# Mother-board.net
KiCad netlist of a schematic drawn in EAGLE
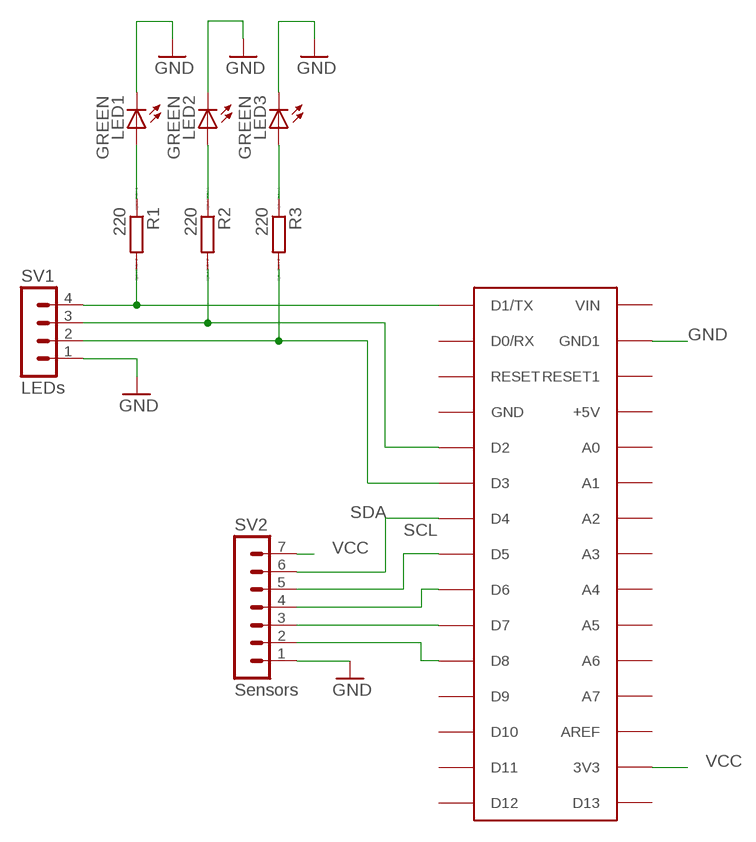
[diagram p0: schematic, sheet 1]

(export (version "E")
  (design (tool "Eeschema 10.0.6"))
  (components
    (comp (ref "LED1")
      (value "GREEN")
      (footprint "eagle-import:LED5MM")
      (libsource (lib "eagle-import") (part "LED5MM"))
    )
    (comp (ref "LED2")
      (value "GREEN")
      (footprint "eagle-import:LED5MM")
      (libsource (lib "eagle-import") (part "LED5MM"))
    )
    (comp (ref "LED3")
      (value "GREEN")
      (footprint "eagle-import:LED5MM")
      (libsource (lib "eagle-import") (part "LED5MM"))
    )
    (comp (ref "R1")
      (value "220")
      (footprint "eagle-import:R1005")
      (libsource (lib "eagle-import") (part "RR1005"))
    )
    (comp (ref "R2")
      (value "220")
      (footprint "eagle-import:R1005")
      (libsource (lib "eagle-import") (part "RR1005"))
    )
    (comp (ref "R3")
      (value "220")
      (footprint "eagle-import:R1005")
      (libsource (lib "eagle-import") (part "RR1005"))
    )
    (comp (ref "SV1")
      (value "LEDs")
      (footprint "eagle-import:MA04-1")
      (libsource (lib "eagle-import") (part "MA04-1"))
    )
    (comp (ref "SV2")
      (value "Sensors")
      (footprint "eagle-import:MA07-1")
      (libsource (lib "eagle-import") (part "MA07-1"))
    )
    (comp (ref "U$1")
      (value "ARDUINONANO")
      (footprint "eagle-import:PDIP-32")
      (libsource (lib "eagle-import") (part "ARDUINONANO"))
    )
  )
  (nets
    (net (code "1") (name "/SCL") (class "Default")
      (node (ref "SV2") (pin "5") (pinfunction "5_5") (pintype "passive"))
      (node (ref "U$1") (pin "D5") (pinfunction "D5_D5") (pintype "bidirectional"))
    )
    (net (code "2") (name "/SDA") (class "Default")
      (node (ref "SV2") (pin "6") (pinfunction "6_6") (pintype "passive"))
      (node (ref "U$1") (pin "D4") (pinfunction "D4_D4") (pintype "bidirectional"))
    )
    (net (code "3") (name "/VCC") (class "Default")
      (node (ref "SV2") (pin "7") (pinfunction "7_7") (pintype "passive"))
      (node (ref "U$1") (pin "3V3") (pinfunction "3V3_3V3") (pintype "bidirectional"))
    )
    (net (code "4") (name "GND") (class "Default")
      (node (ref "LED1") (pin "K") (pinfunction "C_K") (pintype "passive"))
      (node (ref "LED2") (pin "K") (pinfunction "C_K") (pintype "passive"))
      (node (ref "LED3") (pin "K") (pinfunction "C_K") (pintype "passive"))
      (node (ref "SV1") (pin "1") (pinfunction "1_1") (pintype "passive"))
      (node (ref "SV2") (pin "1") (pinfunction "1_1") (pintype "passive"))
      (node (ref "U$1") (pin "GND1") (pinfunction "GND1_GND1") (pintype "bidirectional"))
    )
    (net (code "5") (name "Net-(LED1-PadA)") (class "Default")
      (node (ref "LED1") (pin "A") (pinfunction "A_A") (pintype "passive"))
      (node (ref "R1") (pin "1") (pinfunction "1_1") (pintype "passive"))
    )
    (net (code "6") (name "Net-(LED2-PadA)") (class "Default")
      (node (ref "LED2") (pin "A") (pinfunction "A_A") (pintype "passive"))
      (node (ref "R2") (pin "1") (pinfunction "1_1") (pintype "passive"))
    )
    (net (code "7") (name "Net-(LED3-PadA)") (class "Default")
      (node (ref "LED3") (pin "A") (pinfunction "A_A") (pintype "passive"))
      (node (ref "R3") (pin "1") (pinfunction "1_1") (pintype "passive"))
    )
    (net (code "8") (name "Net-(R1-Pad2)") (class "Default")
      (node (ref "R1") (pin "2") (pinfunction "2_2") (pintype "passive"))
      (node (ref "SV1") (pin "4") (pinfunction "4_4") (pintype "passive"))
      (node (ref "U$1") (pin "D1/TX") (pinfunction "D1/TX_D1/TX") (pintype "bidirectional"))
    )
    (net (code "9") (name "Net-(R2-Pad2)") (class "Default")
      (node (ref "R2") (pin "2") (pinfunction "2_2") (pintype "passive"))
      (node (ref "SV1") (pin "3") (pinfunction "3_3") (pintype "passive"))
      (node (ref "U$1") (pin "D2") (pinfunction "D2_D2") (pintype "bidirectional"))
    )
    (net (code "10") (name "Net-(R3-Pad2)") (class "Default")
      (node (ref "R3") (pin "2") (pinfunction "2_2") (pintype "passive"))
      (node (ref "SV1") (pin "2") (pinfunction "2_2") (pintype "passive"))
      (node (ref "U$1") (pin "D3") (pinfunction "D3_D3") (pintype "bidirectional"))
    )
    (net (code "11") (name "Net-(SV2-Pad2)") (class "Default")
      (node (ref "SV2") (pin "2") (pinfunction "2_2") (pintype "passive"))
      (node (ref "U$1") (pin "D8") (pinfunction "D8_D8") (pintype "bidirectional"))
    )
    (net (code "12") (name "Net-(SV2-Pad3)") (class "Default")
      (node (ref "SV2") (pin "3") (pinfunction "3_3") (pintype "passive"))
      (node (ref "U$1") (pin "D7") (pinfunction "D7_D7") (pintype "bidirectional"))
    )
    (net (code "13") (name "Net-(SV2-Pad4)") (class "Default")
      (node (ref "SV2") (pin "4") (pinfunction "4_4") (pintype "passive"))
      (node (ref "U$1") (pin "D6") (pinfunction "D6_D6") (pintype "bidirectional"))
    )
    (net (code "14") (name "unconnected-(U$1-Pad+5V)") (class "Default")
      (node (ref "U$1") (pin "+5V") (pinfunction "+5V_+5V") (pintype "bidirectional"))
    )
    (net (code "15") (name "unconnected-(U$1-PadA0)") (class "Default")
      (node (ref "U$1") (pin "A0") (pinfunction "A0_A0") (pintype "bidirectional"))
    )
    (net (code "16") (name "unconnected-(U$1-PadA1)") (class "Default")
      (node (ref "U$1") (pin "A1") (pinfunction "A1_A1") (pintype "bidirectional"))
    )
    (net (code "17") (name "unconnected-(U$1-PadA2)") (class "Default")
      (node (ref "U$1") (pin "A2") (pinfunction "A2_A2") (pintype "bidirectional"))
    )
    (net (code "18") (name "unconnected-(U$1-PadA3)") (class "Default")
      (node (ref "U$1") (pin "A3") (pinfunction "A3_A3") (pintype "bidirectional"))
    )
    (net (code "19") (name "unconnected-(U$1-PadA4)") (class "Default")
      (node (ref "U$1") (pin "A4") (pinfunction "A4_A4") (pintype "bidirectional"))
    )
    (net (code "20") (name "unconnected-(U$1-PadA5)") (class "Default")
      (node (ref "U$1") (pin "A5") (pinfunction "A5_A5") (pintype "bidirectional"))
    )
    (net (code "21") (name "unconnected-(U$1-PadA6)") (class "Default")
      (node (ref "U$1") (pin "A6") (pinfunction "A6_A6") (pintype "bidirectional"))
    )
    (net (code "22") (name "unconnected-(U$1-PadA7)") (class "Default")
      (node (ref "U$1") (pin "A7") (pinfunction "A7_A7") (pintype "bidirectional"))
    )
    (net (code "23") (name "unconnected-(U$1-PadAREF)") (class "Default")
      (node (ref "U$1") (pin "AREF") (pinfunction "AREF_AREF") (pintype "bidirectional"))
    )
    (net (code "24") (name "unconnected-(U$1-PadD0{slash}RX)") (class "Default")
      (node (ref "U$1") (pin "D0/RX") (pinfunction "D0/RX_D0/RX") (pintype "bidirectional"))
    )
    (net (code "25") (name "unconnected-(U$1-PadD9)") (class "Default")
      (node (ref "U$1") (pin "D9") (pinfunction "D9_D9") (pintype "bidirectional"))
    )
    (net (code "26") (name "unconnected-(U$1-PadD10)") (class "Default")
      (node (ref "U$1") (pin "D10") (pinfunction "D10_D10") (pintype "bidirectional"))
    )
    (net (code "27") (name "unconnected-(U$1-PadD11)") (class "Default")
      (node (ref "U$1") (pin "D11") (pinfunction "D11_D11") (pintype "bidirectional"))
    )
    (net (code "28") (name "unconnected-(U$1-PadD12)") (class "Default")
      (node (ref "U$1") (pin "D12") (pinfunction "D12_D12") (pintype "bidirectional"))
    )
    (net (code "29") (name "unconnected-(U$1-PadD13)") (class "Default")
      (node (ref "U$1") (pin "D13") (pinfunction "D13_D13") (pintype "bidirectional"))
    )
    (net (code "30") (name "unconnected-(U$1-PadGND)") (class "Default")
      (node (ref "U$1") (pin "GND") (pinfunction "GND_GND") (pintype "bidirectional"))
    )
    (net (code "31") (name "unconnected-(U$1-PadRESET)") (class "Default")
      (node (ref "U$1") (pin "RESET") (pinfunction "RESET_RESET") (pintype "bidirectional"))
    )
    (net (code "32") (name "unconnected-(U$1-PadRESET1)") (class "Default")
      (node (ref "U$1") (pin "RESET1") (pinfunction "RESET1_RESET1") (pintype "bidirectional"))
    )
    (net (code "33") (name "unconnected-(U$1-PadVIN)") (class "Default")
      (node (ref "U$1") (pin "VIN") (pinfunction "VIN_VIN") (pintype "bidirectional"))
    )
  )
)
